# SCFschem.net
KiCad netlist of a schematic drawn in EAGLE
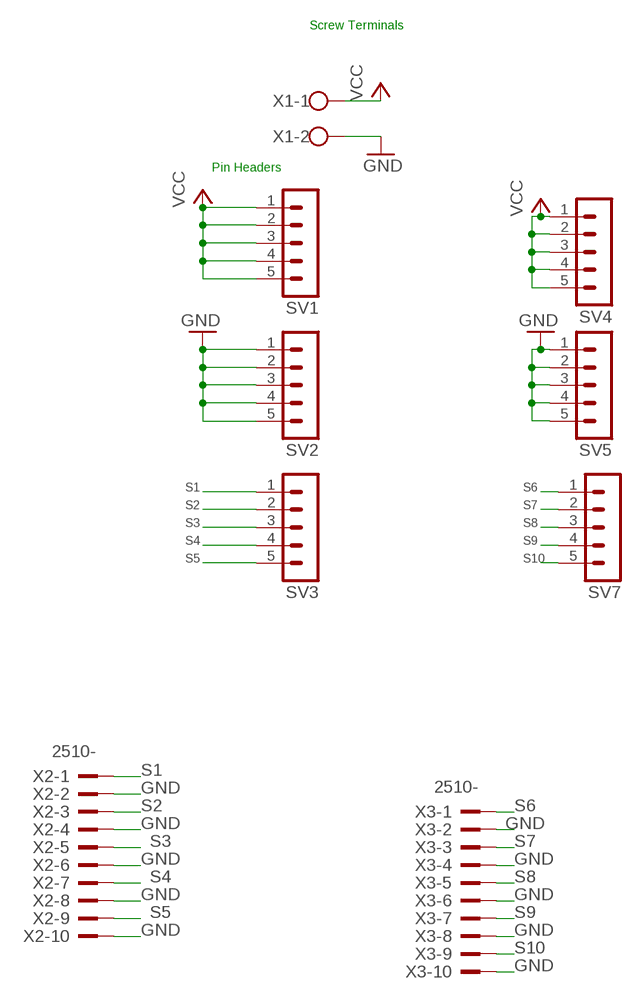
[diagram p0: schematic, sheet 1]

(export (version "E")
  (design (tool "Eeschema 10.0.6"))
  (components
    (comp (ref "SV1")
      (value "MA05-1")
      (footprint "eagle-import:MA05-1")
      (libsource (lib "eagle-import") (part "MA05-1"))
    )
    (comp (ref "SV2")
      (value "MA05-1")
      (footprint "eagle-import:MA05-1")
      (libsource (lib "eagle-import") (part "MA05-1"))
    )
    (comp (ref "SV3")
      (value "MA05-1")
      (footprint "eagle-import:MA05-1")
      (libsource (lib "eagle-import") (part "MA05-1"))
    )
    (comp (ref "SV4")
      (value "MA05-1")
      (footprint "eagle-import:MA05-1")
      (libsource (lib "eagle-import") (part "MA05-1"))
    )
    (comp (ref "SV5")
      (value "MA05-1")
      (footprint "eagle-import:MA05-1")
      (libsource (lib "eagle-import") (part "MA05-1"))
    )
    (comp (ref "SV7")
      (value "MA05-1")
      (footprint "eagle-import:MA05-1")
      (libsource (lib "eagle-import") (part "MA05-1"))
    )
    (comp (ref "X1")
      (value "1X02_5MM_SCREW")
      (footprint "eagle-import:W237-102")
      (fields (field (name "MPN") "237-102"))
      (libsource (lib "eagle-import") (part "1X02_5MM_SCREW"))
    )
    (comp (ref "X2")
      (value "2510-")
      (footprint "eagle-import:PAK100_2500-10")
      (fields (field (name "MF") "3M") (field (name "MPN") "2510-6002UB"))
      (libsource (lib "eagle-import") (part "2510-"))
    )
    (comp (ref "X3")
      (value "2510-")
      (footprint "eagle-import:PAK100_2500-10")
      (fields (field (name "MF") "3M") (field (name "MPN") "2510-6002UB"))
      (libsource (lib "eagle-import") (part "2510-"))
    )
  )
  (nets
    (net (code "1") (name "/S1") (class "Default")
      (node (ref "SV3") (pin "1") (pinfunction "1_1") (pintype "passive"))
      (node (ref "X2") (pin "1") (pinfunction "KL_1") (pintype "passive"))
    )
    (net (code "2") (name "/S2") (class "Default")
      (node (ref "SV3") (pin "2") (pinfunction "2_2") (pintype "passive"))
      (node (ref "X2") (pin "3") (pinfunction "KL_3") (pintype "passive"))
    )
    (net (code "3") (name "/S3") (class "Default")
      (node (ref "SV3") (pin "3") (pinfunction "3_3") (pintype "passive"))
      (node (ref "X2") (pin "5") (pinfunction "KL_5") (pintype "passive"))
    )
    (net (code "4") (name "/S4") (class "Default")
      (node (ref "SV3") (pin "4") (pinfunction "4_4") (pintype "passive"))
      (node (ref "X2") (pin "7") (pinfunction "KL_7") (pintype "passive"))
    )
    (net (code "5") (name "/S5") (class "Default")
      (node (ref "SV3") (pin "5") (pinfunction "5_5") (pintype "passive"))
      (node (ref "X2") (pin "9") (pinfunction "KL_9") (pintype "passive"))
    )
    (net (code "6") (name "/S6") (class "Default")
      (node (ref "SV7") (pin "1") (pinfunction "1_1") (pintype "passive"))
      (node (ref "X3") (pin "1") (pinfunction "KL_1") (pintype "passive"))
    )
    (net (code "7") (name "/S7") (class "Default")
      (node (ref "SV7") (pin "2") (pinfunction "2_2") (pintype "passive"))
      (node (ref "X3") (pin "3") (pinfunction "KL_3") (pintype "passive"))
    )
    (net (code "8") (name "/S8") (class "Default")
      (node (ref "SV7") (pin "3") (pinfunction "3_3") (pintype "passive"))
      (node (ref "X3") (pin "5") (pinfunction "KL_5") (pintype "passive"))
    )
    (net (code "9") (name "/S9") (class "Default")
      (node (ref "SV7") (pin "4") (pinfunction "4_4") (pintype "passive"))
      (node (ref "X3") (pin "7") (pinfunction "KL_7") (pintype "passive"))
    )
    (net (code "10") (name "/S10") (class "Default")
      (node (ref "SV7") (pin "5") (pinfunction "5_5") (pintype "passive"))
      (node (ref "X3") (pin "9") (pinfunction "KL_9") (pintype "passive"))
    )
    (net (code "11") (name "GND") (class "Default")
      (node (ref "SV2") (pin "1") (pinfunction "1_1") (pintype "passive"))
      (node (ref "SV2") (pin "2") (pinfunction "2_2") (pintype "passive"))
      (node (ref "SV2") (pin "3") (pinfunction "3_3") (pintype "passive"))
      (node (ref "SV2") (pin "4") (pinfunction "4_4") (pintype "passive"))
      (node (ref "SV2") (pin "5") (pinfunction "5_5") (pintype "passive"))
      (node (ref "SV5") (pin "1") (pinfunction "1_1") (pintype "passive"))
      (node (ref "SV5") (pin "2") (pinfunction "2_2") (pintype "passive"))
      (node (ref "SV5") (pin "3") (pinfunction "3_3") (pintype "passive"))
      (node (ref "SV5") (pin "4") (pinfunction "4_4") (pintype "passive"))
      (node (ref "SV5") (pin "5") (pinfunction "5_5") (pintype "passive"))
      (node (ref "X1") (pin "2") (pinfunction "KL_2") (pintype "passive"))
      (node (ref "X2") (pin "10") (pinfunction "KL_10") (pintype "passive"))
      (node (ref "X2") (pin "2") (pinfunction "KL_2") (pintype "passive"))
      (node (ref "X2") (pin "4") (pinfunction "KL_4") (pintype "passive"))
      (node (ref "X2") (pin "6") (pinfunction "KL_6") (pintype "passive"))
      (node (ref "X2") (pin "8") (pinfunction "KL_8") (pintype "passive"))
      (node (ref "X3") (pin "10") (pinfunction "KL_10") (pintype "passive"))
      (node (ref "X3") (pin "2") (pinfunction "KL_2") (pintype "passive"))
      (node (ref "X3") (pin "4") (pinfunction "KL_4") (pintype "passive"))
      (node (ref "X3") (pin "6") (pinfunction "KL_6") (pintype "passive"))
      (node (ref "X3") (pin "8") (pinfunction "KL_8") (pintype "passive"))
    )
    (net (code "12") (name "VCC") (class "Default")
      (node (ref "SV1") (pin "1") (pinfunction "1_1") (pintype "passive"))
      (node (ref "SV1") (pin "2") (pinfunction "2_2") (pintype "passive"))
      (node (ref "SV1") (pin "3") (pinfunction "3_3") (pintype "passive"))
      (node (ref "SV1") (pin "4") (pinfunction "4_4") (pintype "passive"))
      (node (ref "SV1") (pin "5") (pinfunction "5_5") (pintype "passive"))
      (node (ref "SV4") (pin "1") (pinfunction "1_1") (pintype "passive"))
      (node (ref "SV4") (pin "2") (pinfunction "2_2") (pintype "passive"))
      (node (ref "SV4") (pin "3") (pinfunction "3_3") (pintype "passive"))
      (node (ref "SV4") (pin "4") (pinfunction "4_4") (pintype "passive"))
      (node (ref "SV4") (pin "5") (pinfunction "5_5") (pintype "passive"))
      (node (ref "X1") (pin "1") (pinfunction "KL_1") (pintype "passive"))
    )
  )
)
